# design1.net
KiCad netlist of a schematic drawn in EAGLE
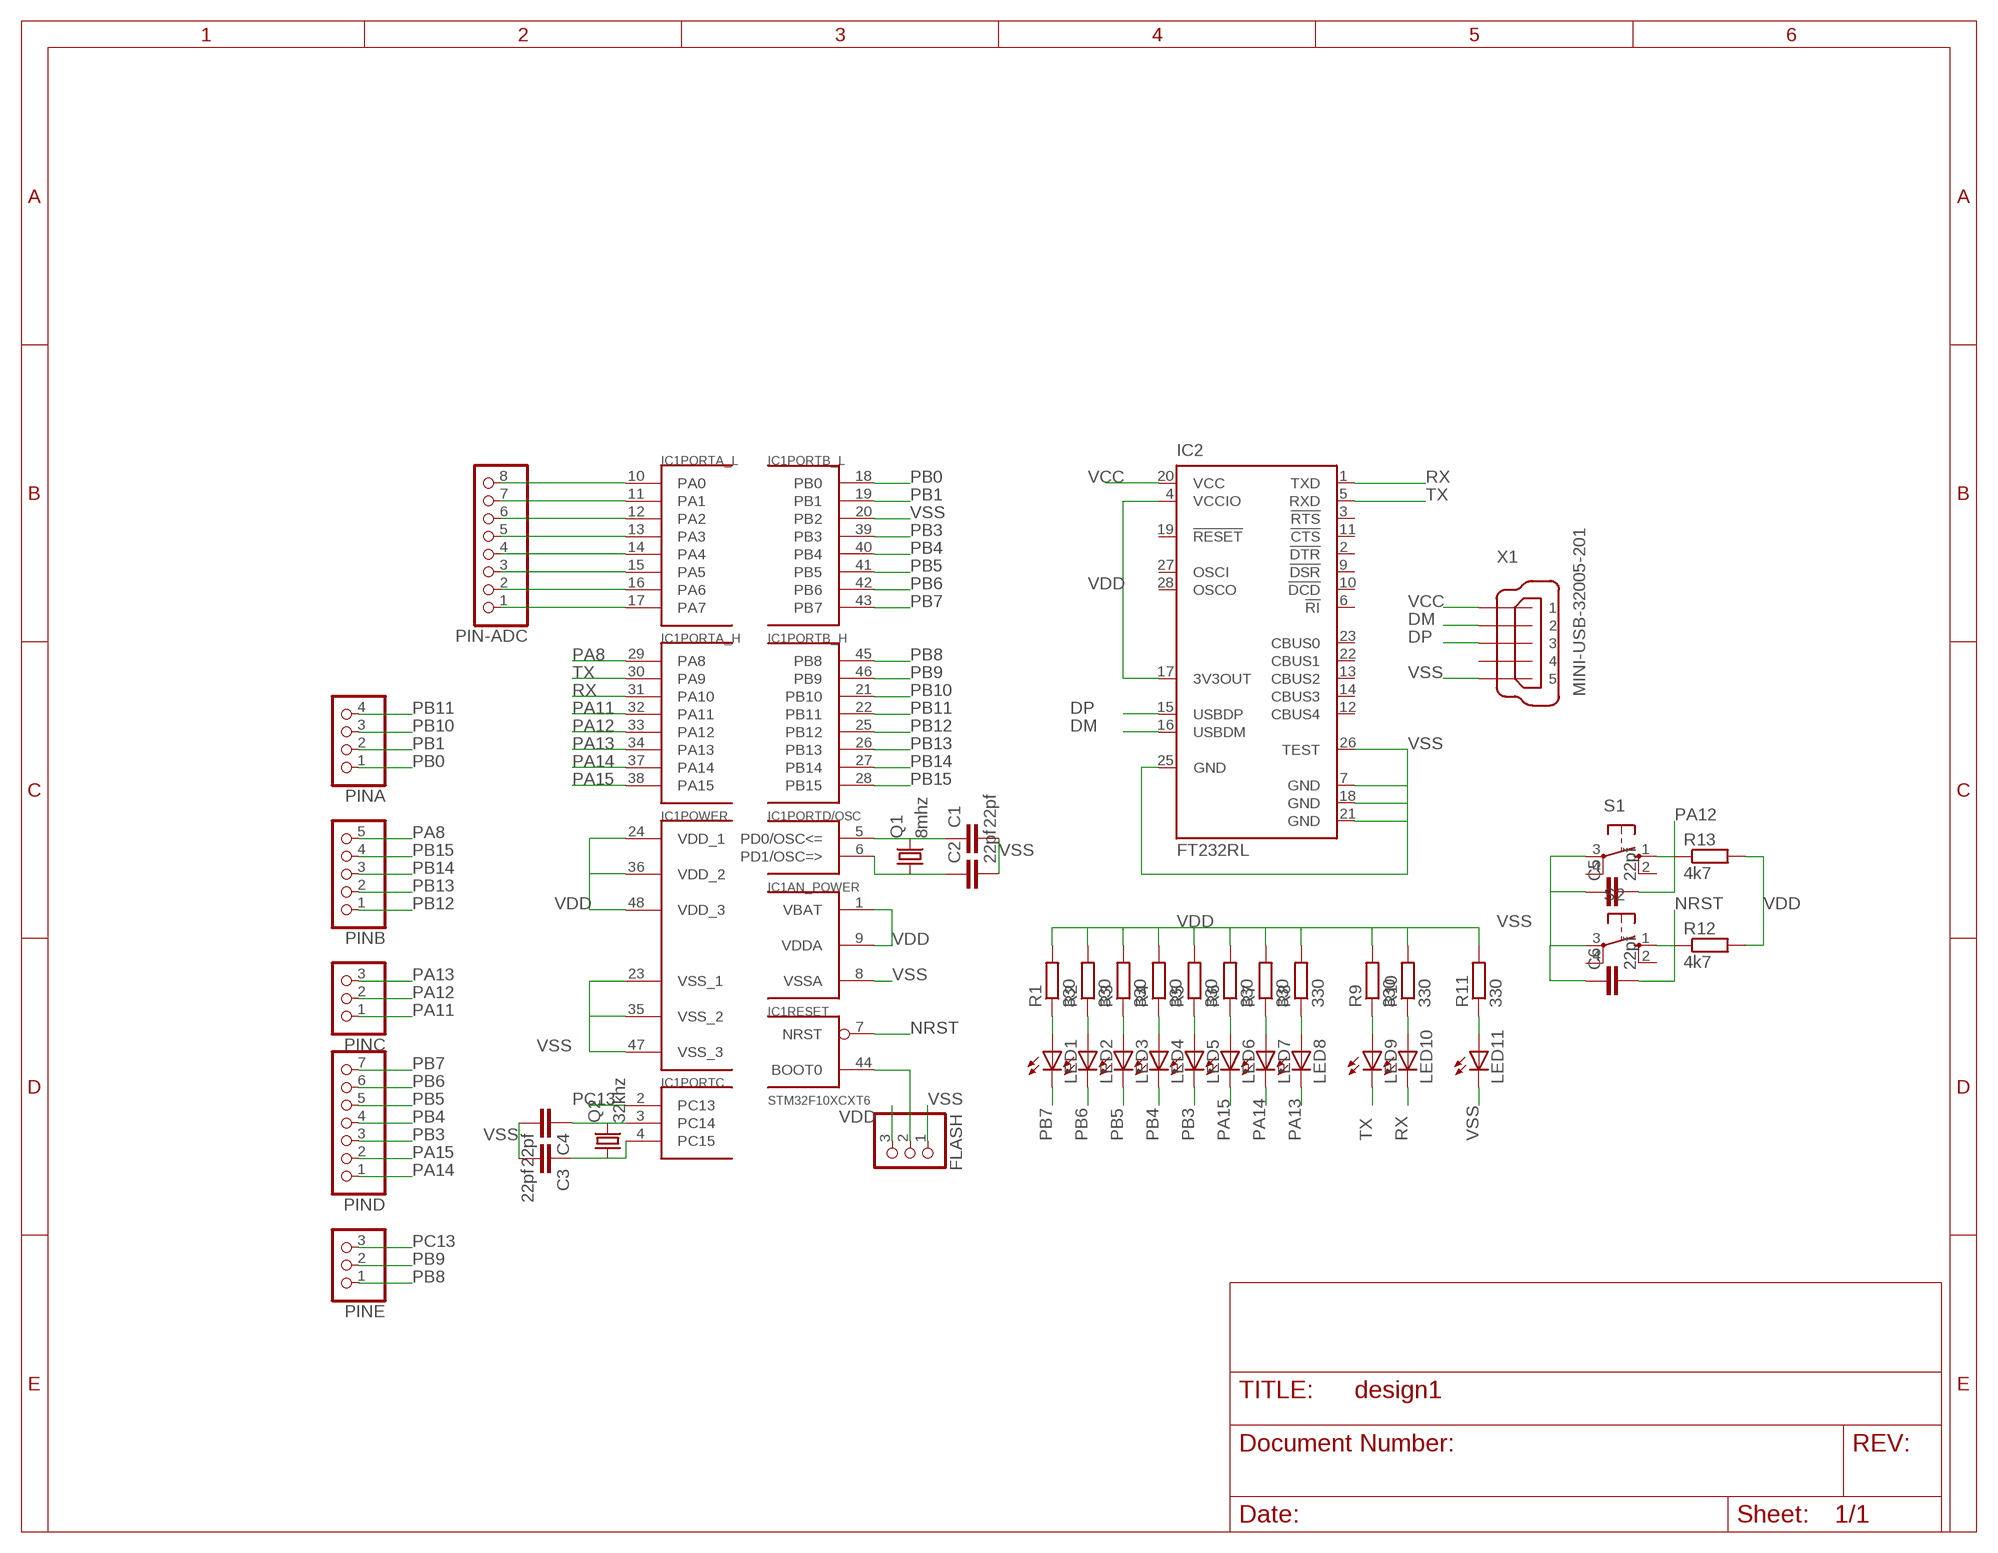
[diagram p0: schematic, sheet 1]

(export (version "E")
  (design (tool "Eeschema 10.0.6"))
  (components
    (comp (ref "C1")
      (value "22pf")
      (footprint "eagle-import:C1206")
      (libsource (lib "eagle-import") (part "C-EUC1206"))
    )
    (comp (ref "C2")
      (value "22pf")
      (footprint "eagle-import:C1206")
      (libsource (lib "eagle-import") (part "C-EUC1206"))
    )
    (comp (ref "C3")
      (value "22pf")
      (footprint "eagle-import:C1206")
      (libsource (lib "eagle-import") (part "C-EUC1206"))
    )
    (comp (ref "C4")
      (value "22pf")
      (footprint "eagle-import:C1206")
      (libsource (lib "eagle-import") (part "C-EUC1206"))
    )
    (comp (ref "C5")
      (value "22pf")
      (footprint "eagle-import:C1206")
      (libsource (lib "eagle-import") (part "C-EUC1206"))
    )
    (comp (ref "C6")
      (value "22pf")
      (footprint "eagle-import:C1206")
      (libsource (lib "eagle-import") (part "C-EUC1206"))
    )
    (comp (ref "FLASH")
      (value "PINHD-1X3")
      (footprint "eagle-import:1X03")
      (libsource (lib "eagle-import") (part "PINHD-1X3"))
    )
    (comp (ref "IC1")
      (value "STM32F10XCXT6")
      (footprint "eagle-import:TQFP48")
      (libsource (lib "eagle-import") (part "STM32F10XCXT6"))
    )
    (comp (ref "IC2")
      (value "FT232RL")
      (footprint "eagle-import:SSOP28")
      (libsource (lib "eagle-import") (part "FT232RL"))
    )
    (comp (ref "LED1")
      (value "LEDSML1206")
      (footprint "eagle-import:SML1206")
      (libsource (lib "eagle-import") (part "LEDSML1206"))
    )
    (comp (ref "LED2")
      (value "LEDSML1206")
      (footprint "eagle-import:SML1206")
      (libsource (lib "eagle-import") (part "LEDSML1206"))
    )
    (comp (ref "LED3")
      (value "LEDSML1206")
      (footprint "eagle-import:SML1206")
      (libsource (lib "eagle-import") (part "LEDSML1206"))
    )
    (comp (ref "LED4")
      (value "LEDSML1206")
      (footprint "eagle-import:SML1206")
      (libsource (lib "eagle-import") (part "LEDSML1206"))
    )
    (comp (ref "LED5")
      (value "LEDSML1206")
      (footprint "eagle-import:SML1206")
      (libsource (lib "eagle-import") (part "LEDSML1206"))
    )
    (comp (ref "LED6")
      (value "LEDSML1206")
      (footprint "eagle-import:SML1206")
      (libsource (lib "eagle-import") (part "LEDSML1206"))
    )
    (comp (ref "LED7")
      (value "LEDSML1206")
      (footprint "eagle-import:SML1206")
      (libsource (lib "eagle-import") (part "LEDSML1206"))
    )
    (comp (ref "LED8")
      (value "LEDSML1206")
      (footprint "eagle-import:SML1206")
      (libsource (lib "eagle-import") (part "LEDSML1206"))
    )
    (comp (ref "LED9")
      (value "LEDSML1206")
      (footprint "eagle-import:SML1206")
      (libsource (lib "eagle-import") (part "LEDSML1206"))
    )
    (comp (ref "LED10")
      (value "LEDSML1206")
      (footprint "eagle-import:SML1206")
      (libsource (lib "eagle-import") (part "LEDSML1206"))
    )
    (comp (ref "LED11")
      (value "LEDSML1206")
      (footprint "eagle-import:SML1206")
      (libsource (lib "eagle-import") (part "LEDSML1206"))
    )
    (comp (ref "PIN-ADC")
      (value "PINHD-1X8")
      (footprint "eagle-import:1X08")
      (libsource (lib "eagle-import") (part "PINHD-1X8"))
    )
    (comp (ref "PINA")
      (value "PINHD-1X4")
      (footprint "eagle-import:1X04")
      (libsource (lib "eagle-import") (part "PINHD-1X4"))
    )
    (comp (ref "PINB")
      (value "PINHD-1X5")
      (footprint "eagle-import:1X05")
      (libsource (lib "eagle-import") (part "PINHD-1X5"))
    )
    (comp (ref "PINC")
      (value "PINHD-1X3")
      (footprint "eagle-import:1X03")
      (libsource (lib "eagle-import") (part "PINHD-1X3"))
    )
    (comp (ref "PIND")
      (value "PINHD-1X7")
      (footprint "eagle-import:1X07")
      (libsource (lib "eagle-import") (part "PINHD-1X7"))
    )
    (comp (ref "PINE")
      (value "PINHD-1X3")
      (footprint "eagle-import:1X03")
      (libsource (lib "eagle-import") (part "PINHD-1X3"))
    )
    (comp (ref "Q1")
      (value "8mhz")
      (footprint "eagle-import:HC49U-V")
      (libsource (lib "eagle-import") (part "CRYSTALHC49U-V"))
    )
    (comp (ref "Q2")
      (value "32khz")
      (footprint "eagle-import:TC26V")
      (libsource (lib "eagle-import") (part "CRYSTALTC26V"))
    )
    (comp (ref "R1")
      (value "330")
      (footprint "eagle-import:R1206")
      (libsource (lib "eagle-import") (part "R-EU_R1206"))
    )
    (comp (ref "R2")
      (value "330")
      (footprint "eagle-import:R1206")
      (libsource (lib "eagle-import") (part "R-EU_R1206"))
    )
    (comp (ref "R3")
      (value "330")
      (footprint "eagle-import:R1206")
      (libsource (lib "eagle-import") (part "R-EU_R1206"))
    )
    (comp (ref "R4")
      (value "330")
      (footprint "eagle-import:R1206")
      (libsource (lib "eagle-import") (part "R-EU_R1206"))
    )
    (comp (ref "R5")
      (value "330")
      (footprint "eagle-import:R1206")
      (libsource (lib "eagle-import") (part "R-EU_R1206"))
    )
    (comp (ref "R6")
      (value "330")
      (footprint "eagle-import:R1206")
      (libsource (lib "eagle-import") (part "R-EU_R1206"))
    )
    (comp (ref "R7")
      (value "330")
      (footprint "eagle-import:R1206")
      (libsource (lib "eagle-import") (part "R-EU_R1206"))
    )
    (comp (ref "R8")
      (value "330")
      (footprint "eagle-import:R1206")
      (libsource (lib "eagle-import") (part "R-EU_R1206"))
    )
    (comp (ref "R9")
      (value "330")
      (footprint "eagle-import:R1206")
      (libsource (lib "eagle-import") (part "R-EU_R1206"))
    )
    (comp (ref "R10")
      (value "330")
      (footprint "eagle-import:R1206")
      (libsource (lib "eagle-import") (part "R-EU_R1206"))
    )
    (comp (ref "R11")
      (value "330")
      (footprint "eagle-import:R1206")
      (libsource (lib "eagle-import") (part "R-EU_R1206"))
    )
    (comp (ref "R12")
      (value "4k7")
      (footprint "eagle-import:R1206")
      (libsource (lib "eagle-import") (part "R-EU_R1206"))
    )
    (comp (ref "R13")
      (value "4k7")
      (footprint "eagle-import:R1206")
      (libsource (lib "eagle-import") (part "R-EU_R1206"))
    )
    (comp (ref "S1")
      (value "10-XX")
      (footprint "eagle-import:B3F-10XX")
      (fields (field (name "MPN") "B3F-1000"))
      (libsource (lib "eagle-import") (part "10-XX"))
    )
    (comp (ref "S2")
      (value "10-XX")
      (footprint "eagle-import:B3F-10XX")
      (fields (field (name "MPN") "B3F-1000"))
      (libsource (lib "eagle-import") (part "10-XX"))
    )
    (comp (ref "X1")
      (value "MINI-USB-32005-201")
      (footprint "eagle-import:32005-201")
      (libsource (lib "eagle-import") (part "MINI-USB-32005-201"))
    )
  )
  (nets
    (net (code "1") (name "/DM") (class "Default")
      (node (ref "IC2") (pin "16") (pinfunction "USBDM_16") (pintype "bidirectional"))
      (node (ref "X1") (pin "2") (pinfunction "2_2") (pintype "passive"))
    )
    (net (code "2") (name "/DP") (class "Default")
      (node (ref "IC2") (pin "15") (pinfunction "USBDP_15") (pintype "bidirectional"))
      (node (ref "X1") (pin "3") (pinfunction "3_3") (pintype "passive"))
    )
    (net (code "3") (name "/NRST") (class "Default")
      (node (ref "C6") (pin "2") (pinfunction "2_2") (pintype "passive"))
      (node (ref "IC1") (pin "7") (pinfunction "NRST_7") (pintype "input"))
      (node (ref "R12") (pin "1") (pinfunction "1_1") (pintype "passive"))
      (node (ref "S2") (pin "1") (pinfunction "S_1") (pintype "passive"))
    )
    (net (code "4") (name "/PA8") (class "Default")
      (node (ref "IC1") (pin "29") (pinfunction "PA8_29") (pintype "bidirectional"))
      (node (ref "PINB") (pin "5") (pinfunction "5_5") (pintype "passive"))
    )
    (net (code "5") (name "/PA11") (class "Default")
      (node (ref "IC1") (pin "32") (pinfunction "PA11_32") (pintype "bidirectional"))
      (node (ref "PINC") (pin "1") (pinfunction "1_1") (pintype "passive"))
    )
    (net (code "6") (name "/PA12") (class "Default")
      (node (ref "C5") (pin "2") (pinfunction "2_2") (pintype "passive"))
      (node (ref "IC1") (pin "33") (pinfunction "PA12_33") (pintype "bidirectional"))
      (node (ref "PINC") (pin "2") (pinfunction "2_2") (pintype "passive"))
      (node (ref "R13") (pin "1") (pinfunction "1_1") (pintype "passive"))
      (node (ref "S1") (pin "1") (pinfunction "S_1") (pintype "passive"))
    )
    (net (code "7") (name "/PA13") (class "Default")
      (node (ref "IC1") (pin "34") (pinfunction "PA13_34") (pintype "bidirectional"))
      (node (ref "LED8") (pin "C") (pinfunction "C_C") (pintype "passive"))
      (node (ref "PINC") (pin "3") (pinfunction "3_3") (pintype "passive"))
    )
    (net (code "8") (name "/PA14") (class "Default")
      (node (ref "IC1") (pin "37") (pinfunction "PA14_37") (pintype "bidirectional"))
      (node (ref "LED7") (pin "C") (pinfunction "C_C") (pintype "passive"))
      (node (ref "PIND") (pin "1") (pinfunction "1_1") (pintype "passive"))
    )
    (net (code "9") (name "/PA15") (class "Default")
      (node (ref "IC1") (pin "38") (pinfunction "PA15_38") (pintype "bidirectional"))
      (node (ref "LED6") (pin "C") (pinfunction "C_C") (pintype "passive"))
      (node (ref "PIND") (pin "2") (pinfunction "2_2") (pintype "passive"))
    )
    (net (code "10") (name "/PB0") (class "Default")
      (node (ref "IC1") (pin "18") (pinfunction "PB0_18") (pintype "bidirectional"))
      (node (ref "PINA") (pin "1") (pinfunction "1_1") (pintype "passive"))
    )
    (net (code "11") (name "/PB1") (class "Default")
      (node (ref "IC1") (pin "19") (pinfunction "PB1_19") (pintype "bidirectional"))
      (node (ref "PINA") (pin "2") (pinfunction "2_2") (pintype "passive"))
    )
    (net (code "12") (name "/PB3") (class "Default")
      (node (ref "IC1") (pin "39") (pinfunction "PB3_39") (pintype "bidirectional"))
      (node (ref "LED5") (pin "C") (pinfunction "C_C") (pintype "passive"))
      (node (ref "PIND") (pin "3") (pinfunction "3_3") (pintype "passive"))
    )
    (net (code "13") (name "/PB4") (class "Default")
      (node (ref "IC1") (pin "40") (pinfunction "PB4_40") (pintype "bidirectional"))
      (node (ref "LED4") (pin "C") (pinfunction "C_C") (pintype "passive"))
      (node (ref "PIND") (pin "4") (pinfunction "4_4") (pintype "passive"))
    )
    (net (code "14") (name "/PB5") (class "Default")
      (node (ref "IC1") (pin "41") (pinfunction "PB5_41") (pintype "bidirectional"))
      (node (ref "LED3") (pin "C") (pinfunction "C_C") (pintype "passive"))
      (node (ref "PIND") (pin "5") (pinfunction "5_5") (pintype "passive"))
    )
    (net (code "15") (name "/PB6") (class "Default")
      (node (ref "IC1") (pin "42") (pinfunction "PB6_42") (pintype "bidirectional"))
      (node (ref "LED2") (pin "C") (pinfunction "C_C") (pintype "passive"))
      (node (ref "PIND") (pin "6") (pinfunction "6_6") (pintype "passive"))
    )
    (net (code "16") (name "/PB7") (class "Default")
      (node (ref "IC1") (pin "43") (pinfunction "PB7_43") (pintype "bidirectional"))
      (node (ref "LED1") (pin "C") (pinfunction "C_C") (pintype "passive"))
      (node (ref "PIND") (pin "7") (pinfunction "7_7") (pintype "passive"))
    )
    (net (code "17") (name "/PB8") (class "Default")
      (node (ref "IC1") (pin "45") (pinfunction "PB8_45") (pintype "bidirectional"))
      (node (ref "PINE") (pin "1") (pinfunction "1_1") (pintype "passive"))
    )
    (net (code "18") (name "/PB9") (class "Default")
      (node (ref "IC1") (pin "46") (pinfunction "PB9_46") (pintype "bidirectional"))
      (node (ref "PINE") (pin "2") (pinfunction "2_2") (pintype "passive"))
    )
    (net (code "19") (name "/PB10") (class "Default")
      (node (ref "IC1") (pin "21") (pinfunction "PB10_21") (pintype "bidirectional"))
      (node (ref "PINA") (pin "3") (pinfunction "3_3") (pintype "passive"))
    )
    (net (code "20") (name "/PB11") (class "Default")
      (node (ref "IC1") (pin "22") (pinfunction "PB11_22") (pintype "bidirectional"))
      (node (ref "PINA") (pin "4") (pinfunction "4_4") (pintype "passive"))
    )
    (net (code "21") (name "/PB12") (class "Default")
      (node (ref "IC1") (pin "25") (pinfunction "PB12_25") (pintype "bidirectional"))
      (node (ref "PINB") (pin "1") (pinfunction "1_1") (pintype "passive"))
    )
    (net (code "22") (name "/PB13") (class "Default")
      (node (ref "IC1") (pin "26") (pinfunction "PB13_26") (pintype "bidirectional"))
      (node (ref "PINB") (pin "2") (pinfunction "2_2") (pintype "passive"))
    )
    (net (code "23") (name "/PB14") (class "Default")
      (node (ref "IC1") (pin "27") (pinfunction "PB14_27") (pintype "bidirectional"))
      (node (ref "PINB") (pin "3") (pinfunction "3_3") (pintype "passive"))
    )
    (net (code "24") (name "/PB15") (class "Default")
      (node (ref "IC1") (pin "28") (pinfunction "PB15_28") (pintype "bidirectional"))
      (node (ref "PINB") (pin "4") (pinfunction "4_4") (pintype "passive"))
    )
    (net (code "25") (name "/PC13") (class "Default")
      (node (ref "IC1") (pin "2") (pinfunction "PC13_2") (pintype "bidirectional"))
      (node (ref "PINE") (pin "3") (pinfunction "3_3") (pintype "passive"))
    )
    (net (code "26") (name "/RX") (class "Default")
      (node (ref "IC1") (pin "31") (pinfunction "PA10_31") (pintype "bidirectional"))
      (node (ref "IC2") (pin "1") (pinfunction "TXD_1") (pintype "output"))
      (node (ref "LED10") (pin "C") (pinfunction "C_C") (pintype "passive"))
    )
    (net (code "27") (name "/TX") (class "Default")
      (node (ref "IC1") (pin "30") (pinfunction "PA9_30") (pintype "bidirectional"))
      (node (ref "IC2") (pin "5") (pinfunction "RXD_5") (pintype "input"))
      (node (ref "LED9") (pin "C") (pinfunction "C_C") (pintype "passive"))
    )
    (net (code "28") (name "/VCC") (class "Default")
      (node (ref "IC2") (pin "20") (pinfunction "VCC_20") (pintype "power_in"))
      (node (ref "X1") (pin "1") (pinfunction "1_1") (pintype "passive"))
    )
    (net (code "29") (name "/VDD") (class "Default")
      (node (ref "FLASH") (pin "3") (pinfunction "3_3") (pintype "passive"))
      (node (ref "IC1") (pin "1") (pinfunction "VBAT_1") (pintype "power_in"))
      (node (ref "IC1") (pin "24") (pinfunction "VDD_1_24") (pintype "power_in"))
      (node (ref "IC1") (pin "36") (pinfunction "VDD_2_36") (pintype "power_in"))
      (node (ref "IC1") (pin "48") (pinfunction "VDD_3_48") (pintype "power_in"))
      (node (ref "IC1") (pin "9") (pinfunction "VDDA_9") (pintype "power_in"))
      (node (ref "IC2") (pin "17") (pinfunction "3V3OUT_17") (pintype "output"))
      (node (ref "IC2") (pin "4") (pinfunction "VCCIO_4") (pintype "power_in"))
      (node (ref "R1") (pin "2") (pinfunction "2_2") (pintype "passive"))
      (node (ref "R10") (pin "2") (pinfunction "2_2") (pintype "passive"))
      (node (ref "R11") (pin "2") (pinfunction "2_2") (pintype "passive"))
      (node (ref "R12") (pin "2") (pinfunction "2_2") (pintype "passive"))
      (node (ref "R13") (pin "2") (pinfunction "2_2") (pintype "passive"))
      (node (ref "R2") (pin "2") (pinfunction "2_2") (pintype "passive"))
      (node (ref "R3") (pin "2") (pinfunction "2_2") (pintype "passive"))
      (node (ref "R4") (pin "2") (pinfunction "2_2") (pintype "passive"))
      (node (ref "R5") (pin "2") (pinfunction "2_2") (pintype "passive"))
      (node (ref "R6") (pin "2") (pinfunction "2_2") (pintype "passive"))
      (node (ref "R7") (pin "2") (pinfunction "2_2") (pintype "passive"))
      (node (ref "R8") (pin "2") (pinfunction "2_2") (pintype "passive"))
      (node (ref "R9") (pin "2") (pinfunction "2_2") (pintype "passive"))
    )
    (net (code "30") (name "/VSS") (class "Default")
      (node (ref "C1") (pin "2") (pinfunction "2_2") (pintype "passive"))
      (node (ref "C2") (pin "2") (pinfunction "2_2") (pintype "passive"))
      (node (ref "C3") (pin "2") (pinfunction "2_2") (pintype "passive"))
      (node (ref "C4") (pin "2") (pinfunction "2_2") (pintype "passive"))
      (node (ref "C5") (pin "1") (pinfunction "1_1") (pintype "passive"))
      (node (ref "C6") (pin "1") (pinfunction "1_1") (pintype "passive"))
      (node (ref "FLASH") (pin "1") (pinfunction "1_1") (pintype "passive"))
      (node (ref "IC1") (pin "20") (pinfunction "PB2_20") (pintype "bidirectional"))
      (node (ref "IC1") (pin "23") (pinfunction "VSS_1_23") (pintype "power_in"))
      (node (ref "IC1") (pin "35") (pinfunction "VSS_2_35") (pintype "power_in"))
      (node (ref "IC1") (pin "47") (pinfunction "VSS_3_47") (pintype "power_in"))
      (node (ref "IC1") (pin "8") (pinfunction "VSSA_8") (pintype "power_in"))
      (node (ref "IC2") (pin "18") (pinfunction "GND_18") (pintype "power_in"))
      (node (ref "IC2") (pin "21") (pinfunction "GND_21") (pintype "power_in"))
      (node (ref "IC2") (pin "25") (pinfunction "GND_25") (pintype "power_in"))
      (node (ref "IC2") (pin "26") (pinfunction "TEST_26") (pintype "input"))
      (node (ref "IC2") (pin "7") (pinfunction "GND_7") (pintype "power_in"))
      (node (ref "LED11") (pin "C") (pinfunction "C_C") (pintype "passive"))
      (node (ref "S1") (pin "3") (pinfunction "P_3") (pintype "passive"))
      (node (ref "S2") (pin "3") (pinfunction "P_3") (pintype "passive"))
      (node (ref "X1") (pin "5") (pinfunction "5_5") (pintype "passive"))
    )
    (net (code "31") (name "Net-(IC1C-PA0)") (class "Default")
      (node (ref "IC1") (pin "10") (pinfunction "PA0_10") (pintype "bidirectional"))
      (node (ref "PIN-ADC") (pin "8") (pinfunction "8_8") (pintype "passive"))
    )
    (net (code "32") (name "Net-(IC1C-PA1)") (class "Default")
      (node (ref "IC1") (pin "11") (pinfunction "PA1_11") (pintype "bidirectional"))
      (node (ref "PIN-ADC") (pin "7") (pinfunction "7_7") (pintype "passive"))
    )
    (net (code "33") (name "Net-(IC1C-PA2)") (class "Default")
      (node (ref "IC1") (pin "12") (pinfunction "PA2_12") (pintype "bidirectional"))
      (node (ref "PIN-ADC") (pin "6") (pinfunction "6_6") (pintype "passive"))
    )
    (net (code "34") (name "Net-(IC1C-PA3)") (class "Default")
      (node (ref "IC1") (pin "13") (pinfunction "PA3_13") (pintype "bidirectional"))
      (node (ref "PIN-ADC") (pin "5") (pinfunction "5_5") (pintype "passive"))
    )
    (net (code "35") (name "Net-(IC1C-PA4)") (class "Default")
      (node (ref "IC1") (pin "14") (pinfunction "PA4_14") (pintype "bidirectional"))
      (node (ref "PIN-ADC") (pin "4") (pinfunction "4_4") (pintype "passive"))
    )
    (net (code "36") (name "Net-(IC1C-PA5)") (class "Default")
      (node (ref "IC1") (pin "15") (pinfunction "PA5_15") (pintype "bidirectional"))
      (node (ref "PIN-ADC") (pin "3") (pinfunction "3_3") (pintype "passive"))
    )
    (net (code "37") (name "Net-(IC1C-PA6)") (class "Default")
      (node (ref "IC1") (pin "16") (pinfunction "PA6_16") (pintype "bidirectional"))
      (node (ref "PIN-ADC") (pin "2") (pinfunction "2_2") (pintype "passive"))
    )
    (net (code "38") (name "Net-(IC1C-PA7)") (class "Default")
      (node (ref "IC1") (pin "17") (pinfunction "PA7_17") (pintype "bidirectional"))
      (node (ref "PIN-ADC") (pin "1") (pinfunction "1_1") (pintype "passive"))
    )
    (net (code "39") (name "Net-(IC1F-PC14)") (class "Default")
      (node (ref "C4") (pin "1") (pinfunction "1_1") (pintype "passive"))
      (node (ref "IC1") (pin "3") (pinfunction "PC14_3") (pintype "bidirectional"))
      (node (ref "Q2") (pin "2") (pinfunction "2_2") (pintype "passive"))
    )
    (net (code "40") (name "Net-(IC1F-PC15)") (class "Default")
      (node (ref "C3") (pin "1") (pinfunction "1_1") (pintype "passive"))
      (node (ref "IC1") (pin "4") (pinfunction "PC15_4") (pintype "bidirectional"))
      (node (ref "Q2") (pin "1") (pinfunction "1_1") (pintype "passive"))
    )
    (net (code "41") (name "Net-(IC1G-PD0{slash}OSC<=)") (class "Default")
      (node (ref "C1") (pin "1") (pinfunction "1_1") (pintype "passive"))
      (node (ref "IC1") (pin "5") (pinfunction "PD0/OSC<=_5") (pintype "bidirectional"))
      (node (ref "Q1") (pin "2") (pinfunction "2_2") (pintype "passive"))
    )
    (net (code "42") (name "Net-(IC1G-PD1{slash}OSC=>)") (class "Default")
      (node (ref "C2") (pin "1") (pinfunction "1_1") (pintype "passive"))
      (node (ref "IC1") (pin "6") (pinfunction "PD1/OSC=>_6") (pintype "bidirectional"))
      (node (ref "Q1") (pin "1") (pinfunction "1_1") (pintype "passive"))
    )
    (net (code "43") (name "Net-(IC1I-BOOT0)") (class "Default")
      (node (ref "FLASH") (pin "2") (pinfunction "2_2") (pintype "passive"))
      (node (ref "IC1") (pin "44") (pinfunction "BOOT0_44") (pintype "input"))
    )
    (net (code "44") (name "Net-(LED1-PadA)") (class "Default")
      (node (ref "LED1") (pin "A") (pinfunction "A_A") (pintype "passive"))
      (node (ref "R1") (pin "1") (pinfunction "1_1") (pintype "passive"))
    )
    (net (code "45") (name "Net-(LED2-PadA)") (class "Default")
      (node (ref "LED2") (pin "A") (pinfunction "A_A") (pintype "passive"))
      (node (ref "R2") (pin "1") (pinfunction "1_1") (pintype "passive"))
    )
    (net (code "46") (name "Net-(LED3-PadA)") (class "Default")
      (node (ref "LED3") (pin "A") (pinfunction "A_A") (pintype "passive"))
      (node (ref "R3") (pin "1") (pinfunction "1_1") (pintype "passive"))
    )
    (net (code "47") (name "Net-(LED4-PadA)") (class "Default")
      (node (ref "LED4") (pin "A") (pinfunction "A_A") (pintype "passive"))
      (node (ref "R4") (pin "1") (pinfunction "1_1") (pintype "passive"))
    )
    (net (code "48") (name "Net-(LED5-PadA)") (class "Default")
      (node (ref "LED5") (pin "A") (pinfunction "A_A") (pintype "passive"))
      (node (ref "R5") (pin "1") (pinfunction "1_1") (pintype "passive"))
    )
    (net (code "49") (name "Net-(LED6-PadA)") (class "Default")
      (node (ref "LED6") (pin "A") (pinfunction "A_A") (pintype "passive"))
      (node (ref "R6") (pin "1") (pinfunction "1_1") (pintype "passive"))
    )
    (net (code "50") (name "Net-(LED7-PadA)") (class "Default")
      (node (ref "LED7") (pin "A") (pinfunction "A_A") (pintype "passive"))
      (node (ref "R7") (pin "1") (pinfunction "1_1") (pintype "passive"))
    )
    (net (code "51") (name "Net-(LED8-PadA)") (class "Default")
      (node (ref "LED8") (pin "A") (pinfunction "A_A") (pintype "passive"))
      (node (ref "R8") (pin "1") (pinfunction "1_1") (pintype "passive"))
    )
    (net (code "52") (name "Net-(LED9-PadA)") (class "Default")
      (node (ref "LED9") (pin "A") (pinfunction "A_A") (pintype "passive"))
      (node (ref "R9") (pin "1") (pinfunction "1_1") (pintype "passive"))
    )
    (net (code "53") (name "Net-(LED10-PadA)") (class "Default")
      (node (ref "LED10") (pin "A") (pinfunction "A_A") (pintype "passive"))
      (node (ref "R10") (pin "1") (pinfunction "1_1") (pintype "passive"))
    )
    (net (code "54") (name "Net-(LED11-PadA)") (class "Default")
      (node (ref "LED11") (pin "A") (pinfunction "A_A") (pintype "passive"))
      (node (ref "R11") (pin "1") (pinfunction "1_1") (pintype "passive"))
    )
    (net (code "55") (name "unconnected-(IC2-CBUS0-Pad23)") (class "Default")
      (node (ref "IC2") (pin "23") (pinfunction "CBUS0_23") (pintype "bidirectional"))
    )
    (net (code "56") (name "unconnected-(IC2-CBUS1-Pad22)") (class "Default")
      (node (ref "IC2") (pin "22") (pinfunction "CBUS1_22") (pintype "bidirectional"))
    )
    (net (code "57") (name "unconnected-(IC2-CBUS2-Pad13)") (class "Default")
      (node (ref "IC2") (pin "13") (pinfunction "CBUS2_13") (pintype "bidirectional"))
    )
    (net (code "58") (name "unconnected-(IC2-CBUS3-Pad14)") (class "Default")
      (node (ref "IC2") (pin "14") (pinfunction "CBUS3_14") (pintype "bidirectional"))
    )
    (net (code "59") (name "unconnected-(IC2-CBUS4-Pad12)") (class "Default")
      (node (ref "IC2") (pin "12") (pinfunction "CBUS4_12") (pintype "bidirectional"))
    )
    (net (code "60") (name "unconnected-(IC2-OSCI-Pad27)") (class "Default")
      (node (ref "IC2") (pin "27") (pinfunction "OSCI_27") (pintype "input"))
    )
    (net (code "61") (name "unconnected-(IC2-OSCO-Pad28)") (class "Default")
      (node (ref "IC2") (pin "28") (pinfunction "OSCO_28") (pintype "output"))
    )
    (net (code "62") (name "unconnected-(IC2-~{CTS}-Pad11)") (class "Default")
      (node (ref "IC2") (pin "11") (pinfunction "~{CTS}_11") (pintype "input"))
    )
    (net (code "63") (name "unconnected-(IC2-~{DCD}-Pad10)") (class "Default")
      (node (ref "IC2") (pin "10") (pinfunction "~{DCD}_10") (pintype "input"))
    )
    (net (code "64") (name "unconnected-(IC2-~{DSR}-Pad9)") (class "Default")
      (node (ref "IC2") (pin "9") (pinfunction "~{DSR}_9") (pintype "input"))
    )
    (net (code "65") (name "unconnected-(IC2-~{DTR}-Pad2)") (class "Default")
      (node (ref "IC2") (pin "2") (pinfunction "~{DTR}_2") (pintype "output"))
    )
    (net (code "66") (name "unconnected-(IC2-~{RESET}-Pad19)") (class "Default")
      (node (ref "IC2") (pin "19") (pinfunction "~{RESET}_19") (pintype "input"))
    )
    (net (code "67") (name "unconnected-(IC2-~{RI}-Pad6)") (class "Default")
      (node (ref "IC2") (pin "6") (pinfunction "~{RI}_6") (pintype "input"))
    )
    (net (code "68") (name "unconnected-(IC2-~{RTS}-Pad3)") (class "Default")
      (node (ref "IC2") (pin "3") (pinfunction "~{RTS}_3") (pintype "output"))
    )
    (net (code "69") (name "unconnected-(S1-P1-Pad4)") (class "Default")
      (node (ref "S1") (pin "4") (pinfunction "P1_4") (pintype "passive"))
    )
    (net (code "70") (name "unconnected-(S1-S1-Pad2)") (class "Default")
      (node (ref "S1") (pin "2") (pinfunction "S1_2") (pintype "passive"))
    )
    (net (code "71") (name "unconnected-(S2-P1-Pad4)") (class "Default")
      (node (ref "S2") (pin "4") (pinfunction "P1_4") (pintype "passive"))
    )
    (net (code "72") (name "unconnected-(S2-S1-Pad2)") (class "Default")
      (node (ref "S2") (pin "2") (pinfunction "S1_2") (pintype "passive"))
    )
    (net (code "73") (name "unconnected-(X1-Pad4)") (class "Default")
      (node (ref "X1") (pin "4") (pinfunction "4_4") (pintype "passive"))
    )
  )
)
